# B-CAN-giraffe_v2.net
KiCad netlist of a schematic drawn in EAGLE
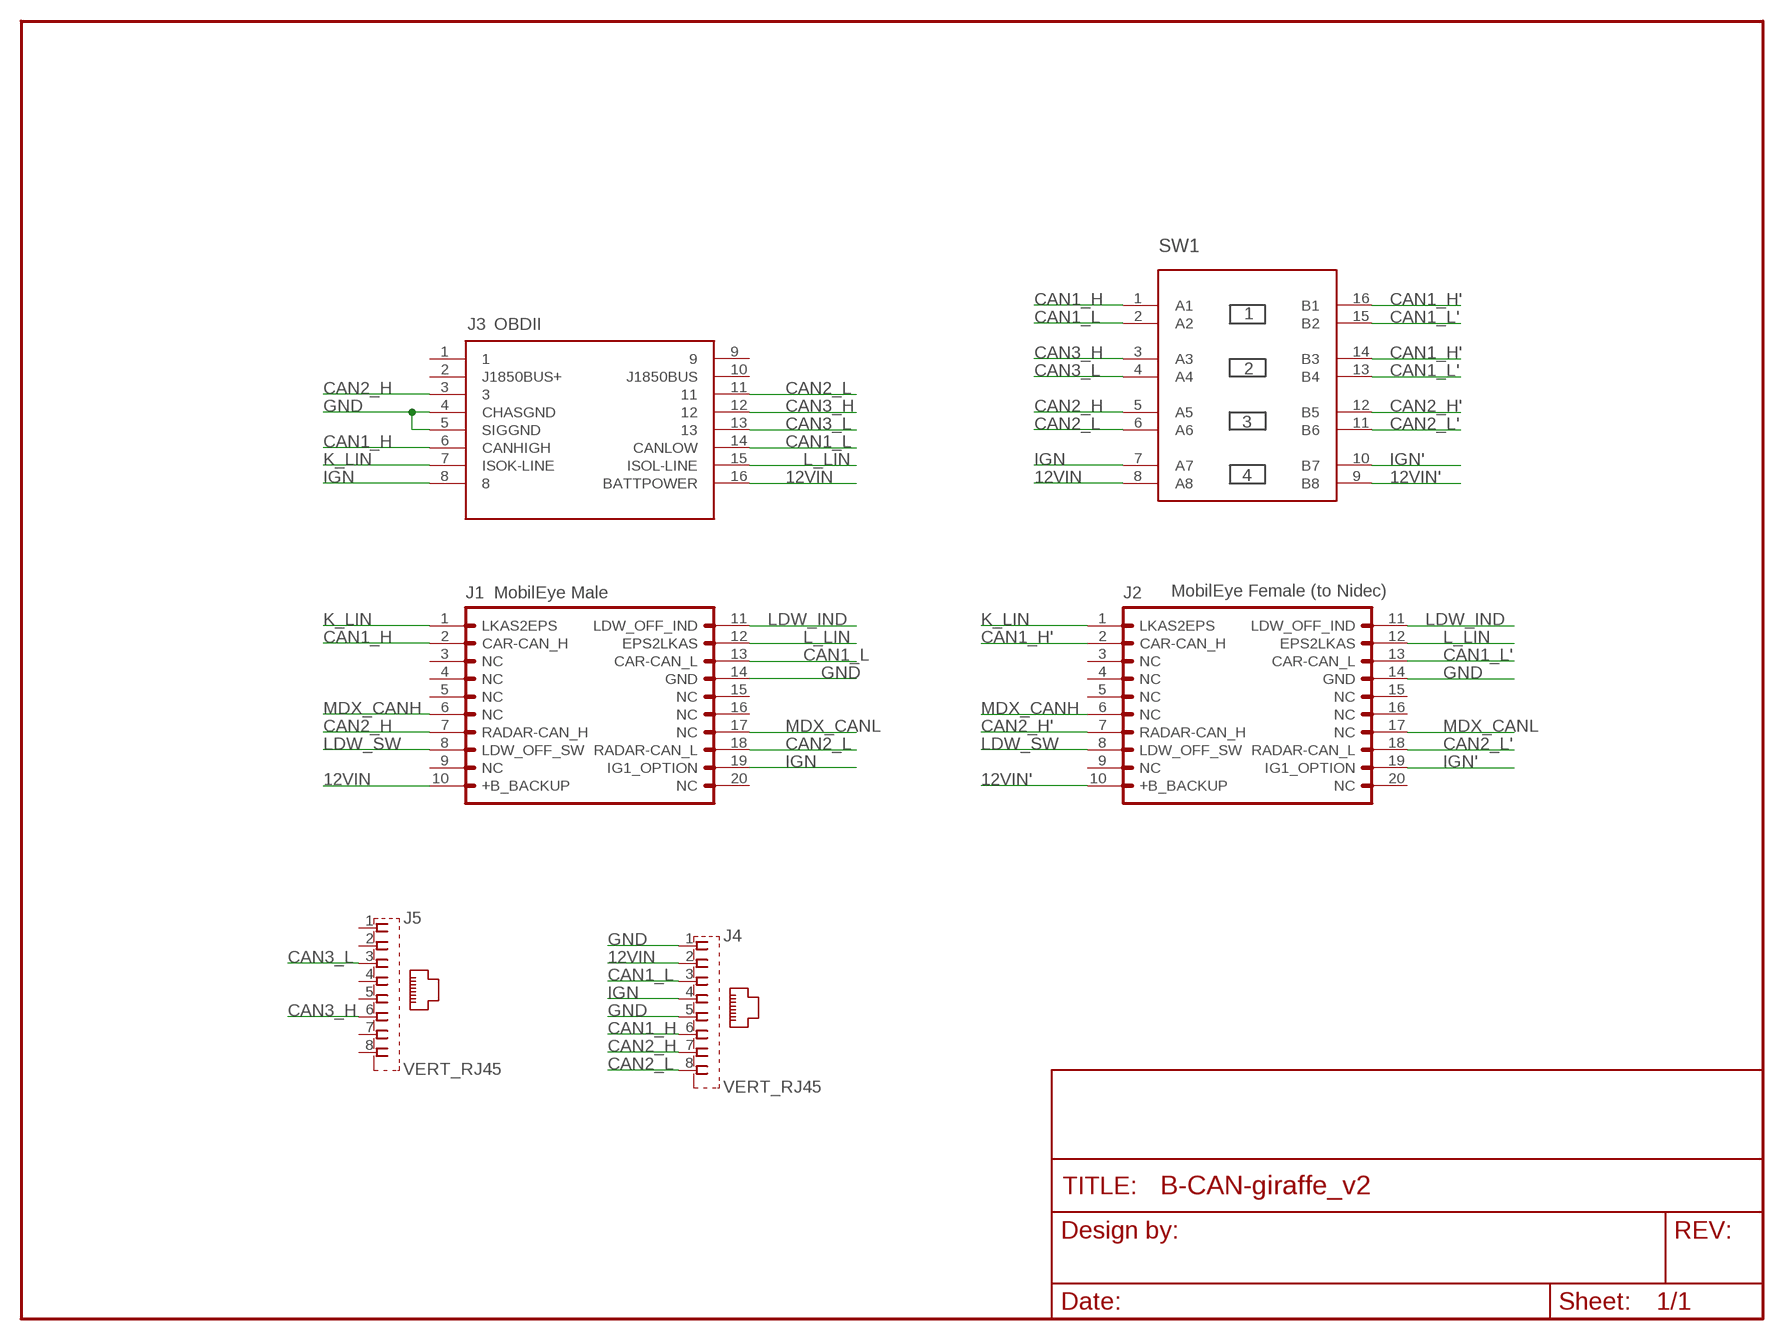
[diagram p0: schematic, sheet 1]

(export (version "E")
  (design (tool "Eeschema 10.0.6"))
  (components
    (comp (ref "FRAME1")
      (value "FRAME-LETTERNO_PACKAGE")
      (footprint "eagle-import:DUMMY")
      (fields (field (name "DESIGNER") "Nobody"))
      (libsource (lib "eagle-import") (part "FRAME-LETTERNO_PACKAGE"))
    )
    (comp (ref "J1")
      (value "MOBILEYERAMALE")
      (footprint "eagle-import:2X10(RA)")
      (libsource (lib "eagle-import") (part "MOBILEYERAMALE"))
    )
    (comp (ref "J2")
      (value "MOBILEYEFEMALE")
      (footprint "eagle-import:2X10(JAE_FEMALE)")
      (libsource (lib "eagle-import") (part "MOBILEYEFEMALE"))
    )
    (comp (ref "J3")
      (value "OBDII-FEMALE-CUT")
      (footprint "eagle-import:OBDII-FEMALE-MIDCUT")
      (libsource (lib "eagle-import") (part "OBDII-FEMALE-CUT"))
    )
    (comp (ref "J4")
      (value "VERT_RJ45")
      (footprint "eagle-import:GLX-S-88M")
      (libsource (lib "eagle-import") (part "VERT_RJ45"))
    )
    (comp (ref "J5")
      (value "VERT_RJ45")
      (footprint "eagle-import:GLX-S-88M")
      (libsource (lib "eagle-import") (part "comma.ai_2652900_VERT_RJ45"))
    )
    (comp (ref "SW1")
      (value "4XDPSTSMT")
      (footprint "eagle-import:4-DPST")
      (libsource (lib "eagle-import") (part "4XDPSTSMT"))
    )
  )
  (nets
    (net (code "1") (name "/12VIN") (class "Default")
      (node (ref "J1") (pin "10") (pinfunction "+B_BACKUP_10") (pintype "bidirectional"))
      (node (ref "J3") (pin "16") (pinfunction "BATTPOWER_16") (pintype "bidirectional"))
      (node (ref "J4") (pin "2") (pinfunction "2_2") (pintype "passive"))
      (node (ref "SW1") (pin "8") (pinfunction "A8_8") (pintype "bidirectional"))
    )
    (net (code "2") (name "/12VIN'") (class "Default")
      (node (ref "J2") (pin "10") (pinfunction "+B_BACKUP_10") (pintype "bidirectional"))
      (node (ref "SW1") (pin "9") (pinfunction "B8_9") (pintype "bidirectional"))
    )
    (net (code "3") (name "/CAN1_H") (class "Default")
      (node (ref "J1") (pin "2") (pinfunction "CAR-CAN_H_2") (pintype "bidirectional"))
      (node (ref "J3") (pin "6") (pinfunction "CANHIGH_6") (pintype "bidirectional"))
      (node (ref "J4") (pin "6") (pinfunction "6_6") (pintype "passive"))
      (node (ref "SW1") (pin "1") (pinfunction "A1_1") (pintype "bidirectional"))
    )
    (net (code "4") (name "/CAN1_H'") (class "Default")
      (node (ref "J2") (pin "2") (pinfunction "CAR-CAN_H_2") (pintype "bidirectional"))
      (node (ref "SW1") (pin "14") (pinfunction "B3_14") (pintype "bidirectional"))
      (node (ref "SW1") (pin "16") (pinfunction "B1_16") (pintype "bidirectional"))
    )
    (net (code "5") (name "/CAN1_L") (class "Default")
      (node (ref "J1") (pin "13") (pinfunction "CAR-CAN_L_13") (pintype "bidirectional"))
      (node (ref "J3") (pin "14") (pinfunction "CANLOW_14") (pintype "bidirectional"))
      (node (ref "J4") (pin "3") (pinfunction "3_3") (pintype "passive"))
      (node (ref "SW1") (pin "2") (pinfunction "A2_2") (pintype "bidirectional"))
    )
    (net (code "6") (name "/CAN1_L'") (class "Default")
      (node (ref "J2") (pin "13") (pinfunction "CAR-CAN_L_13") (pintype "bidirectional"))
      (node (ref "SW1") (pin "13") (pinfunction "B4_13") (pintype "bidirectional"))
      (node (ref "SW1") (pin "15") (pinfunction "B2_15") (pintype "bidirectional"))
    )
    (net (code "7") (name "/CAN2_H") (class "Default")
      (node (ref "J1") (pin "7") (pinfunction "RADAR-CAN_H_7") (pintype "bidirectional"))
      (node (ref "J3") (pin "3") (pinfunction "3_3") (pintype "bidirectional"))
      (node (ref "J4") (pin "7") (pinfunction "7_7") (pintype "passive"))
      (node (ref "SW1") (pin "5") (pinfunction "A5_5") (pintype "bidirectional"))
    )
    (net (code "8") (name "/CAN2_H'") (class "Default")
      (node (ref "J2") (pin "7") (pinfunction "RADAR-CAN_H_7") (pintype "bidirectional"))
      (node (ref "SW1") (pin "12") (pinfunction "B5_12") (pintype "bidirectional"))
    )
    (net (code "9") (name "/CAN2_L") (class "Default")
      (node (ref "J1") (pin "18") (pinfunction "RADAR-CAN_L_18") (pintype "bidirectional"))
      (node (ref "J3") (pin "11") (pinfunction "11_11") (pintype "bidirectional"))
      (node (ref "J4") (pin "8") (pinfunction "8_8") (pintype "passive"))
      (node (ref "SW1") (pin "6") (pinfunction "A6_6") (pintype "bidirectional"))
    )
    (net (code "10") (name "/CAN2_L'") (class "Default")
      (node (ref "J2") (pin "18") (pinfunction "RADAR-CAN_L_18") (pintype "bidirectional"))
      (node (ref "SW1") (pin "11") (pinfunction "B6_11") (pintype "bidirectional"))
    )
    (net (code "11") (name "/CAN3_H") (class "Default")
      (node (ref "J3") (pin "12") (pinfunction "12_12") (pintype "bidirectional"))
      (node (ref "J5") (pin "6") (pinfunction "6_6") (pintype "passive"))
      (node (ref "SW1") (pin "3") (pinfunction "A3_3") (pintype "bidirectional"))
    )
    (net (code "12") (name "/CAN3_L") (class "Default")
      (node (ref "J3") (pin "13") (pinfunction "13_13") (pintype "bidirectional"))
      (node (ref "J5") (pin "3") (pinfunction "3_3") (pintype "passive"))
      (node (ref "SW1") (pin "4") (pinfunction "A4_4") (pintype "bidirectional"))
    )
    (net (code "13") (name "/GND") (class "Default")
      (node (ref "J1") (pin "14") (pinfunction "GND_14") (pintype "bidirectional"))
      (node (ref "J2") (pin "14") (pinfunction "GND_14") (pintype "bidirectional"))
      (node (ref "J3") (pin "4") (pinfunction "CHASGND_4") (pintype "bidirectional"))
      (node (ref "J3") (pin "5") (pinfunction "SIGGND_5") (pintype "bidirectional"))
      (node (ref "J4") (pin "1") (pinfunction "1_1") (pintype "passive"))
      (node (ref "J4") (pin "5") (pinfunction "5_5") (pintype "passive"))
    )
    (net (code "14") (name "/IGN") (class "Default")
      (node (ref "J1") (pin "19") (pinfunction "IG1_OPTION_19") (pintype "bidirectional"))
      (node (ref "J3") (pin "8") (pinfunction "8_8") (pintype "bidirectional"))
      (node (ref "J4") (pin "4") (pinfunction "4_4") (pintype "passive"))
      (node (ref "SW1") (pin "7") (pinfunction "A7_7") (pintype "bidirectional"))
    )
    (net (code "15") (name "/IGN'") (class "Default")
      (node (ref "J2") (pin "19") (pinfunction "IG1_OPTION_19") (pintype "bidirectional"))
      (node (ref "SW1") (pin "10") (pinfunction "B7_10") (pintype "bidirectional"))
    )
    (net (code "16") (name "/K_LIN") (class "Default")
      (node (ref "J1") (pin "1") (pinfunction "LKAS2EPS_1") (pintype "bidirectional"))
      (node (ref "J2") (pin "1") (pinfunction "LKAS2EPS_1") (pintype "bidirectional"))
      (node (ref "J3") (pin "7") (pinfunction "ISOK-LINE_7") (pintype "bidirectional"))
    )
    (net (code "17") (name "/LDW_IND") (class "Default")
      (node (ref "J1") (pin "11") (pinfunction "LDW_OFF_IND_11") (pintype "bidirectional"))
      (node (ref "J2") (pin "11") (pinfunction "LDW_OFF_IND_11") (pintype "bidirectional"))
    )
    (net (code "18") (name "/LDW_SW") (class "Default")
      (node (ref "J1") (pin "8") (pinfunction "LDW_OFF_SW_8") (pintype "bidirectional"))
      (node (ref "J2") (pin "8") (pinfunction "LDW_OFF_SW_8") (pintype "bidirectional"))
    )
    (net (code "19") (name "/L_LIN") (class "Default")
      (node (ref "J1") (pin "12") (pinfunction "EPS2LKAS_12") (pintype "bidirectional"))
      (node (ref "J2") (pin "12") (pinfunction "EPS2LKAS_12") (pintype "bidirectional"))
      (node (ref "J3") (pin "15") (pinfunction "ISOL-LINE_15") (pintype "bidirectional"))
    )
    (net (code "20") (name "/MDX_CANH") (class "Default")
      (node (ref "J1") (pin "6") (pinfunction "NC_6") (pintype "bidirectional"))
      (node (ref "J2") (pin "6") (pinfunction "NC_6") (pintype "bidirectional"))
    )
    (net (code "21") (name "/MDX_CANL") (class "Default")
      (node (ref "J1") (pin "17") (pinfunction "NC_17") (pintype "bidirectional"))
      (node (ref "J2") (pin "17") (pinfunction "NC_17") (pintype "bidirectional"))
    )
    (net (code "22") (name "unconnected-(J1-NC-Pad3)") (class "Default")
      (node (ref "J1") (pin "3") (pinfunction "NC_3") (pintype "bidirectional"))
    )
    (net (code "23") (name "unconnected-(J1-NC-Pad4)") (class "Default")
      (node (ref "J1") (pin "4") (pinfunction "NC_4") (pintype "bidirectional"))
    )
    (net (code "24") (name "unconnected-(J1-NC-Pad5)") (class "Default")
      (node (ref "J1") (pin "5") (pinfunction "NC_5") (pintype "bidirectional"))
    )
    (net (code "25") (name "unconnected-(J1-NC-Pad9)") (class "Default")
      (node (ref "J1") (pin "9") (pinfunction "NC_9") (pintype "bidirectional"))
    )
    (net (code "26") (name "unconnected-(J1-NC-Pad15)") (class "Default")
      (node (ref "J1") (pin "15") (pinfunction "NC_15") (pintype "bidirectional"))
    )
    (net (code "27") (name "unconnected-(J1-NC-Pad16)") (class "Default")
      (node (ref "J1") (pin "16") (pinfunction "NC_16") (pintype "bidirectional"))
    )
    (net (code "28") (name "unconnected-(J1-NC-Pad20)") (class "Default")
      (node (ref "J1") (pin "20") (pinfunction "NC_20") (pintype "bidirectional"))
    )
    (net (code "29") (name "unconnected-(J2-NC-Pad3)") (class "Default")
      (node (ref "J2") (pin "3") (pinfunction "NC_3") (pintype "bidirectional"))
    )
    (net (code "30") (name "unconnected-(J2-NC-Pad4)") (class "Default")
      (node (ref "J2") (pin "4") (pinfunction "NC_4") (pintype "bidirectional"))
    )
    (net (code "31") (name "unconnected-(J2-NC-Pad5)") (class "Default")
      (node (ref "J2") (pin "5") (pinfunction "NC_5") (pintype "bidirectional"))
    )
    (net (code "32") (name "unconnected-(J2-NC-Pad9)") (class "Default")
      (node (ref "J2") (pin "9") (pinfunction "NC_9") (pintype "bidirectional"))
    )
    (net (code "33") (name "unconnected-(J2-NC-Pad15)") (class "Default")
      (node (ref "J2") (pin "15") (pinfunction "NC_15") (pintype "bidirectional"))
    )
    (net (code "34") (name "unconnected-(J2-NC-Pad16)") (class "Default")
      (node (ref "J2") (pin "16") (pinfunction "NC_16") (pintype "bidirectional"))
    )
    (net (code "35") (name "unconnected-(J2-NC-Pad20)") (class "Default")
      (node (ref "J2") (pin "20") (pinfunction "NC_20") (pintype "bidirectional"))
    )
    (net (code "36") (name "unconnected-(J3-J1850BUS+-Pad2)") (class "Default")
      (node (ref "J3") (pin "2") (pinfunction "J1850BUS+_2") (pintype "bidirectional"))
    )
    (net (code "37") (name "unconnected-(J3-J1850BUS-Pad10)") (class "Default")
      (node (ref "J3") (pin "10") (pinfunction "J1850BUS_10") (pintype "bidirectional"))
    )
    (net (code "38") (name "unconnected-(J3-Pad1)") (class "Default")
      (node (ref "J3") (pin "1") (pinfunction "1_1") (pintype "bidirectional"))
    )
    (net (code "39") (name "unconnected-(J3-Pad9)") (class "Default")
      (node (ref "J3") (pin "9") (pinfunction "9_9") (pintype "bidirectional"))
    )
    (net (code "40") (name "unconnected-(J5-Pad1)") (class "Default")
      (node (ref "J5") (pin "1") (pinfunction "1_1") (pintype "passive"))
    )
    (net (code "41") (name "unconnected-(J5-Pad2)") (class "Default")
      (node (ref "J5") (pin "2") (pinfunction "2_2") (pintype "passive"))
    )
    (net (code "42") (name "unconnected-(J5-Pad4)") (class "Default")
      (node (ref "J5") (pin "4") (pinfunction "4_4") (pintype "passive"))
    )
    (net (code "43") (name "unconnected-(J5-Pad5)") (class "Default")
      (node (ref "J5") (pin "5") (pinfunction "5_5") (pintype "passive"))
    )
    (net (code "44") (name "unconnected-(J5-Pad7)") (class "Default")
      (node (ref "J5") (pin "7") (pinfunction "7_7") (pintype "passive"))
    )
    (net (code "45") (name "unconnected-(J5-Pad8)") (class "Default")
      (node (ref "J5") (pin "8") (pinfunction "8_8") (pintype "passive"))
    )
  )
)
